# LightSaber.net
KiCad netlist of a schematic drawn in Altium Designer
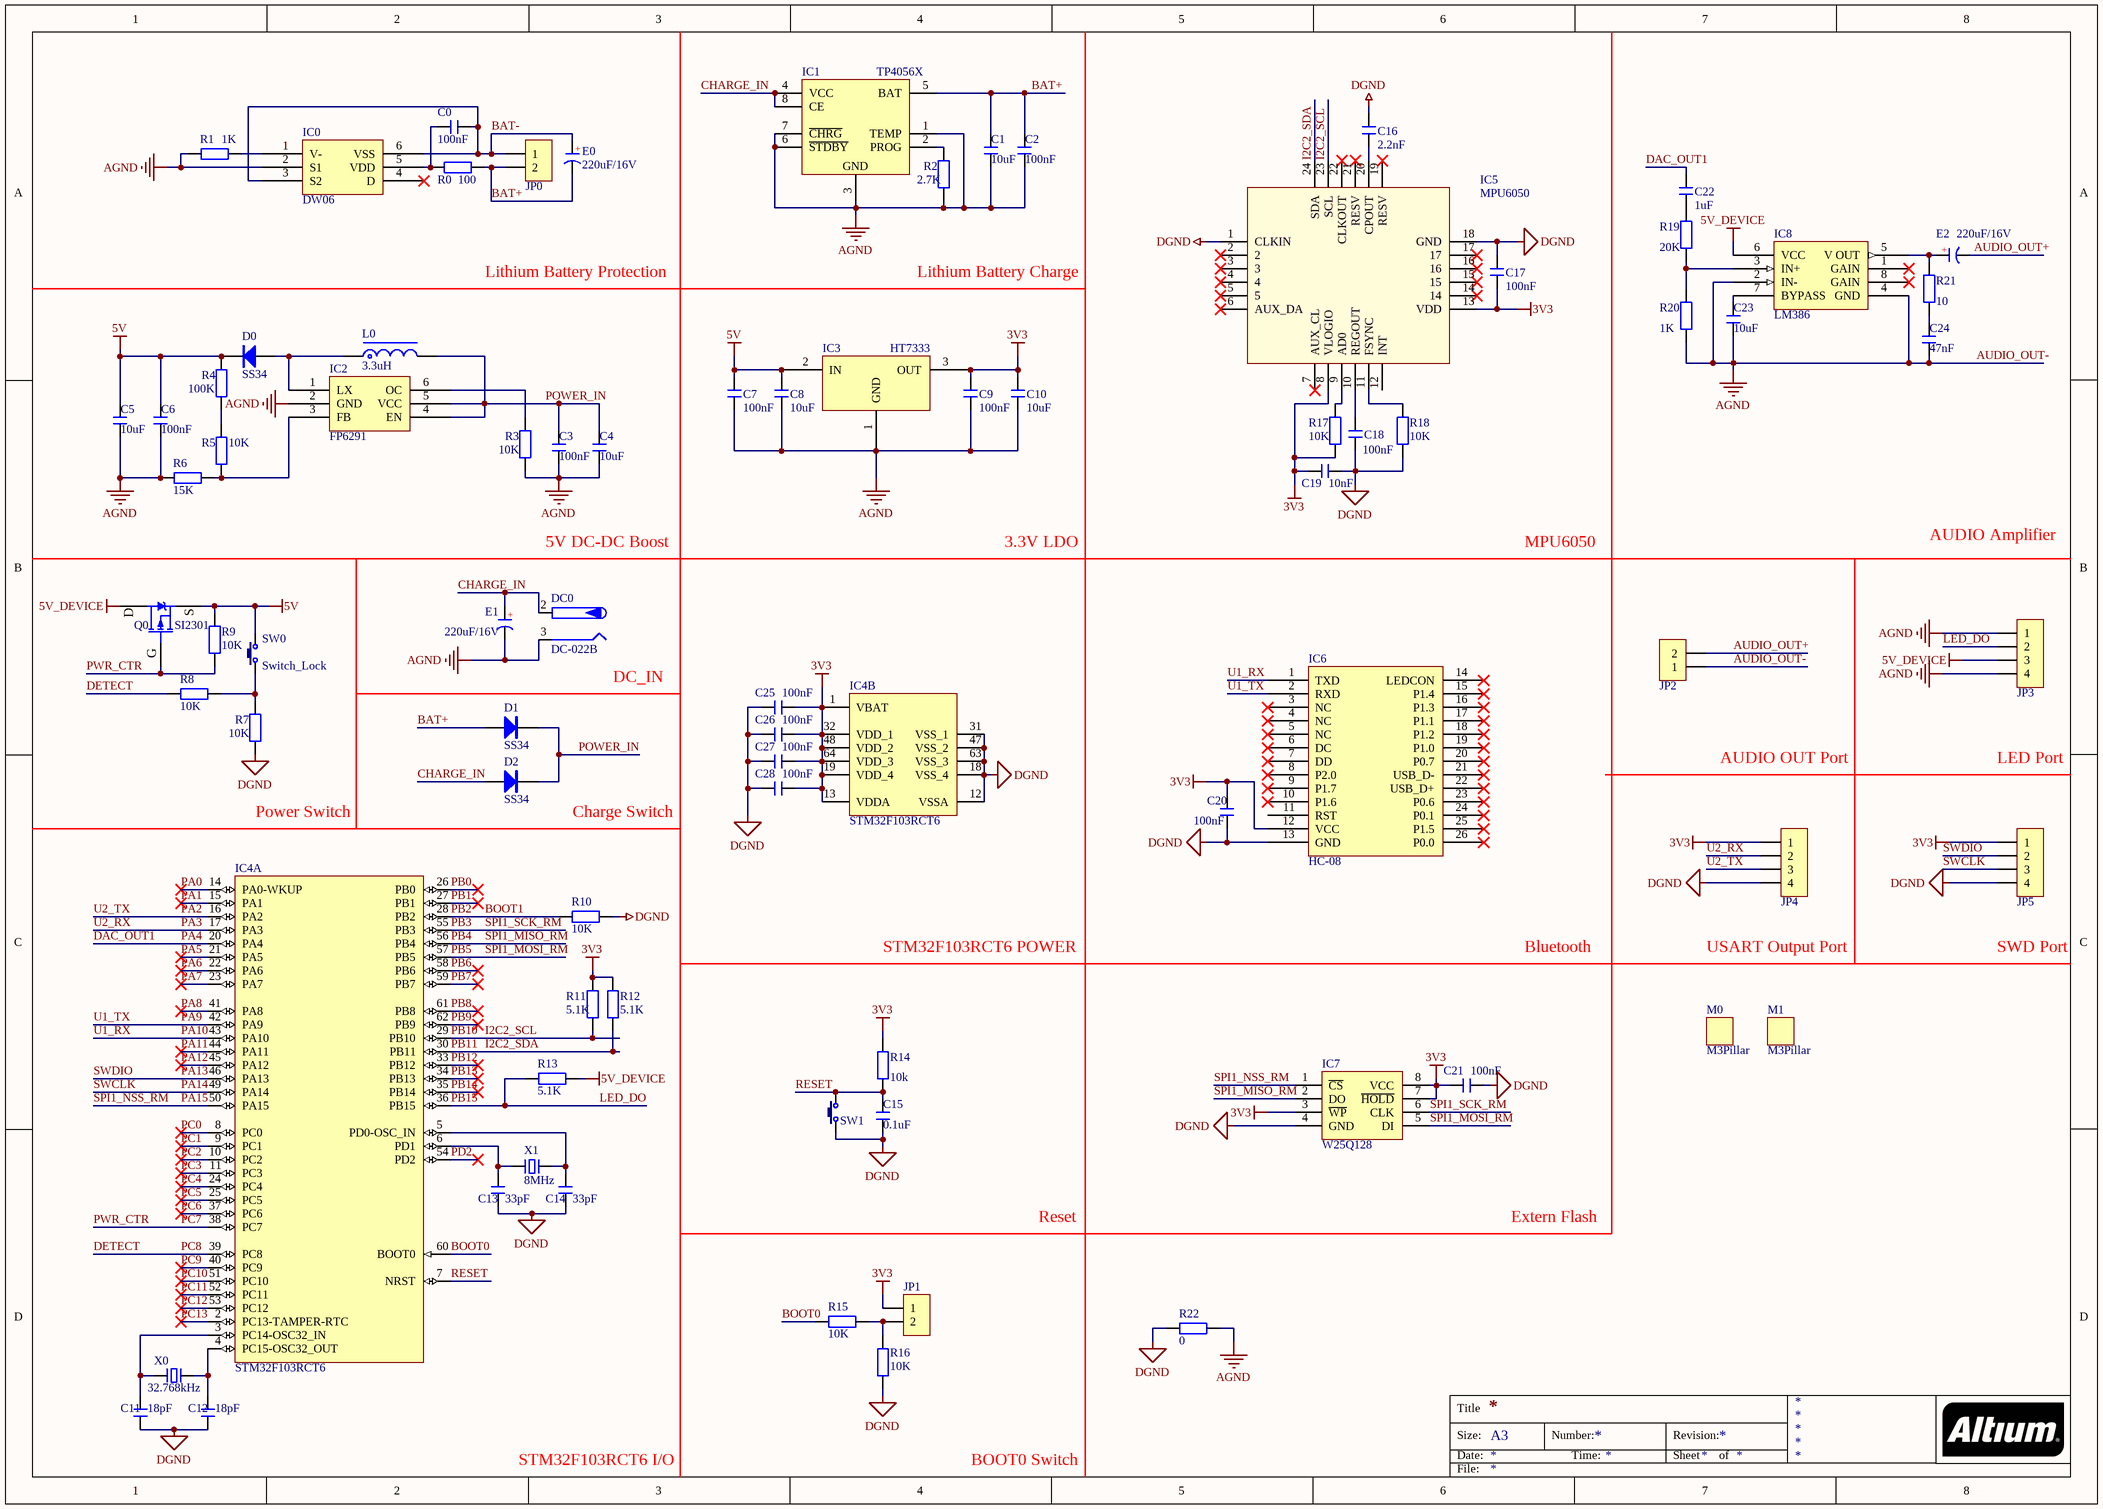
[diagram p0: LightSaber.SchDoc]

(export (version "E")
  (design (tool "Eeschema 10.0.6"))
  (components
    (comp (ref "C0")
      (value "100nF")
      (footprint "C 0603_L")
      (description "无极性贴片电容")
      (libsource (lib "0.1 - 电阻-电容-电感") (part "C"))
    )
    (comp (ref "C1")
      (value "10uF")
      (footprint "C 0603_L")
      (description "无极性贴片电容")
      (libsource (lib "0.1 - 电阻-电容-电感") (part "C"))
    )
    (comp (ref "C2")
      (value "100nF")
      (footprint "C 0603_L")
      (description "无极性贴片电容")
      (libsource (lib "0.1 - 电阻-电容-电感") (part "C"))
    )
    (comp (ref "C3")
      (value "100nF")
      (footprint "C 0603_L")
      (description "无极性贴片电容")
      (libsource (lib "0.1 - 电阻-电容-电感") (part "C"))
    )
    (comp (ref "C4")
      (value "10uF")
      (footprint "C 0603_L")
      (description "无极性贴片电容")
      (libsource (lib "0.1 - 电阻-电容-电感") (part "C"))
    )
    (comp (ref "C5")
      (value "10uF")
      (footprint "C 0603_L")
      (description "无极性贴片电容")
      (libsource (lib "0.1 - 电阻-电容-电感") (part "C"))
    )
    (comp (ref "C6")
      (value "100nF")
      (footprint "C 0603_L")
      (description "无极性贴片电容")
      (libsource (lib "0.1 - 电阻-电容-电感") (part "C"))
    )
    (comp (ref "C7")
      (value "100nF")
      (footprint "C 0603_L")
      (description "无极性贴片电容")
      (libsource (lib "0.1 - 电阻-电容-电感") (part "C"))
    )
    (comp (ref "C8")
      (value "10uF")
      (footprint "C 0603_L")
      (description "无极性贴片电容")
      (libsource (lib "0.1 - 电阻-电容-电感") (part "C"))
    )
    (comp (ref "C9")
      (value "100nF")
      (footprint "C 0603_L")
      (description "无极性贴片电容")
      (libsource (lib "0.1 - 电阻-电容-电感") (part "C"))
    )
    (comp (ref "C10")
      (value "10uF")
      (footprint "C 0603_L")
      (description "无极性贴片电容")
      (libsource (lib "0.1 - 电阻-电容-电感") (part "C"))
    )
    (comp (ref "C11")
      (value "18pF")
      (footprint "C 0603_L")
      (description "无极性贴片电容")
      (libsource (lib "0.1 - 电阻-电容-电感") (part "C"))
    )
    (comp (ref "C12")
      (value "18pF")
      (footprint "C 0603_L")
      (description "无极性贴片电容")
      (libsource (lib "0.1 - 电阻-电容-电感") (part "C"))
    )
    (comp (ref "C13")
      (value "33pF")
      (footprint "C 0603_L")
      (description "无极性贴片电容")
      (libsource (lib "0.1 - 电阻-电容-电感") (part "C"))
    )
    (comp (ref "C14")
      (value "33pF")
      (footprint "C 0603_L")
      (description "无极性贴片电容")
      (libsource (lib "0.1 - 电阻-电容-电感") (part "C"))
    )
    (comp (ref "C15")
      (value "0.1uF")
      (footprint "C 0603_L")
      (description "无极性贴片电容")
      (libsource (lib "0.1 - 电阻-电容-电感") (part "C"))
    )
    (comp (ref "C16")
      (value "2.2nF")
      (footprint "C 0603_L")
      (description "无极性贴片电容")
      (libsource (lib "0.1 - 电阻-电容-电感") (part "C"))
    )
    (comp (ref "C17")
      (value "100nF")
      (footprint "C 0603_L")
      (description "无极性贴片电容")
      (libsource (lib "0.1 - 电阻-电容-电感") (part "C"))
    )
    (comp (ref "C18")
      (value "100nF")
      (footprint "C 0603_L")
      (description "无极性贴片电容")
      (libsource (lib "0.1 - 电阻-电容-电感") (part "C"))
    )
    (comp (ref "C19")
      (value "10nF")
      (footprint "C 0603_L")
      (description "无极性贴片电容")
      (libsource (lib "0.1 - 电阻-电容-电感") (part "C"))
    )
    (comp (ref "C20")
      (value "100nF")
      (footprint "C 0603_L")
      (description "无极性贴片电容")
      (libsource (lib "0.1 - 电阻-电容-电感") (part "C"))
    )
    (comp (ref "C21")
      (value "100nF")
      (footprint "C 0603_L")
      (description "无极性贴片电容")
      (libsource (lib "0.1 - 电阻-电容-电感") (part "C"))
    )
    (comp (ref "C22")
      (value "1uF")
      (footprint "C 0603_L")
      (description "无极性贴片电容")
      (libsource (lib "0.1 - 电阻-电容-电感") (part "C"))
    )
    (comp (ref "C23")
      (value "10uF")
      (footprint "C 0603_L")
      (description "无极性贴片电容")
      (libsource (lib "0.1 - 电阻-电容-电感") (part "C"))
    )
    (comp (ref "C24")
      (value "47nF")
      (footprint "C 0603_L")
      (description "无极性贴片电容")
      (libsource (lib "0.1 - 电阻-电容-电感") (part "C"))
    )
    (comp (ref "C25")
      (value "100nF")
      (footprint "C 0603_L")
      (description "无极性贴片电容")
      (libsource (lib "0.1 - 电阻-电容-电感") (part "C"))
    )
    (comp (ref "C26")
      (value "100nF")
      (footprint "C 0603_L")
      (description "无极性贴片电容")
      (libsource (lib "0.1 - 电阻-电容-电感") (part "C"))
    )
    (comp (ref "C27")
      (value "100nF")
      (footprint "C 0603_L")
      (description "无极性贴片电容")
      (libsource (lib "0.1 - 电阻-电容-电感") (part "C"))
    )
    (comp (ref "C28")
      (value "100nF")
      (footprint "C 0603_L")
      (description "无极性贴片电容")
      (libsource (lib "0.1 - 电阻-电容-电感") (part "C"))
    )
    (comp (ref "D0")
      (value "SS34")
      (footprint "SMA")
      (description "肖特基二极管")
      (libsource (lib "0.2 -  二极管-整流桥") (part "SS34"))
    )
    (comp (ref "D1")
      (value "SS34")
      (footprint "SMA")
      (description "肖特基二极管")
      (libsource (lib "0.2 -  二极管-整流桥") (part "SS34"))
    )
    (comp (ref "D2")
      (value "SS34")
      (footprint "SMA")
      (description "肖特基二极管")
      (libsource (lib "0.2 -  二极管-整流桥") (part "SS34"))
    )
    (comp (ref "DC0") (value "DC-022B") (footprint "DC-022B") (libsource (lib "LightSaber") (part "DC-022B")))
    (comp (ref "E0")
      (value "220uF/16V")
      (footprint "CAP 2.5*6.3*7 - BK")
      (description "直插电解电容")
      (libsource (lib "0.1 - 电阻-电容-电感") (part "C-CAP"))
    )
    (comp (ref "E1")
      (value "220uF/16V")
      (footprint "CAP 2.5*6.3*7 - BK")
      (description "直插电解电容")
      (libsource (lib "0.1 - 电阻-电容-电感") (part "C-CAP"))
    )
    (comp (ref "E2")
      (value "220uF/16V")
      (footprint "CAP 2.5*6.3*7 - BK")
      (description "直插电解电容")
      (libsource (lib "") (part "C-CAP_1"))
    )
    (comp (ref "IC0") (value "DW06") (footprint "SOT23-6N") (libsource (lib "LightSaber") (part "DW06")))
    (comp (ref "IC1")
      (value "TP4056X")
      (footprint "SOP8_N")
      (description "锂电池充电管理")
      (libsource (lib "1.2 - 电源类芯片") (part "TP4056"))
    )
    (comp (ref "IC2")
      (value "FP6291")
      (footprint "SOT23-6")
      (libsource (lib "altium-import") (part "root_0_FP6291_"))
    )
    (comp (ref "IC3") (value "HT7333") (footprint "SOT89_M") (libsource (lib "LightSaber") (part "HT7333")))
    (comp (ref "IC4")
      (value "STM32F103RCT6")
      (footprint "LQFP64_N")
      (libsource (lib "2.3 - STM32 F1系列MCU 集成库") (part "STM32F103RCT6"))
    )
    (comp (ref "IC5")
      (value "MPU6050")
      (footprint "QFN_24")
      (description "三轴加速度+三轴陀螺仪")
      (libsource (lib "主集成库") (part "MPU6050"))
    )
    (comp (ref "IC6") (value "HC-08") (footprint "HC-08V20/22/41") (libsource (lib "HC-08") (part "HC-08")))
    (comp (ref "IC7")
      (value "W25Q128")
      (footprint "SOP8W_N")
      (description "外置Flash")
      (fields (field (name "版权归属") "源创客"))
      (libsource (lib "1.1 - 常见芯片") (part "W25Qxx"))
    )
    (comp (ref "IC8") (value "LM386") (footprint "SOP8") (libsource (lib "7.1 - 模拟符号") (part "LM386")))
    (comp (ref "JP0")
      (value "HDR-1X2")
      (footprint "XH2.54-LI-2P")
      (description "2P接插件")
      (fields (field (name "版权归属") "源创客"))
      (libsource (lib "") (part "Header 2_1"))
    )
    (comp (ref "JP1")
      (value "HDR-1X2")
      (footprint "HDR2.54-LI-2P")
      (description "2P接插件")
      (fields (field (name "版权归属") "源创客"))
      (libsource (lib "") (part "Header 2_1"))
    )
    (comp (ref "JP2")
      (value "HDR-1X2")
      (footprint "XH2.54-LI-2P")
      (description "2P接插件")
      (fields (field (name "版权归属") "源创客"))
      (libsource (lib "5.3 - 接插件-脚距2.54 (100mil) ") (part "Header 2"))
    )
    (comp (ref "JP3")
      (value "HDR-1X4")
      (footprint "XH2.54-LI-4P")
      (description "4P接插件")
      (fields (field (name "版权归属") "源创客"))
      (libsource (lib "5.3 - 接插件-脚距2.54 (100mil) ") (part "Header 4"))
    )
    (comp (ref "JP4")
      (value "HDR-1X4")
      (footprint "HDR2.54-LI-4P")
      (description "4P接插件")
      (fields (field (name "版权归属") "源创客"))
      (libsource (lib "5.3 - 接插件-脚距2.54 (100mil) ") (part "Header 4"))
    )
    (comp (ref "JP5")
      (value "HDR-1X4")
      (footprint "HDR2.54-LI-4P")
      (description "4P接插件")
      (fields (field (name "版权归属") "源创客"))
      (libsource (lib "5.3 - 接插件-脚距2.54 (100mil) ") (part "Header 4"))
    )
    (comp (ref "L0")
      (value "3.3uH")
      (footprint "PK0406")
      (description "工字电感")
      (libsource (lib "0.1 - 电阻-电容-电感") (part "L-PK"))
    )
    (comp (ref "M0") (value "M3Pillar") (footprint "M3x4_L") (libsource (lib "LightSaber") (part "M3Pillar")))
    (comp (ref "M1") (value "M3Pillar") (footprint "M3x4_L") (libsource (lib "LightSaber") (part "M3Pillar")))
    (comp (ref "Q0")
      (value "SI2301")
      (footprint "SOT23-3N")
      (description "P沟道场效应管")
      (libsource (lib "0.5 - 场效应管-可控硅") (part "SI2301"))
    )
    (comp (ref "R0")
      (value "100")
      (footprint "R 0603_L")
      (description "贴片电阻")
      (fields (field (name "版权归属") "黄晶宝石"))
      (libsource (lib "0.1 - 电阻-电容-电感") (part "R"))
    )
    (comp (ref "R1")
      (value "1K")
      (footprint "R 0603_L")
      (description "贴片电阻")
      (fields (field (name "版权归属") "黄晶宝石"))
      (libsource (lib "0.1 - 电阻-电容-电感") (part "R"))
    )
    (comp (ref "R2")
      (value "2.7K")
      (footprint "R 0603_L")
      (description "贴片电阻")
      (fields (field (name "版权归属") "黄晶宝石"))
      (libsource (lib "0.1 - 电阻-电容-电感") (part "R"))
    )
    (comp (ref "R3")
      (value "10K")
      (footprint "R 0603_L")
      (description "贴片电阻")
      (fields (field (name "版权归属") "黄晶宝石"))
      (libsource (lib "0.1 - 电阻-电容-电感") (part "R"))
    )
    (comp (ref "R4")
      (value "100K")
      (footprint "R 0603_L")
      (description "贴片电阻")
      (fields (field (name "版权归属") "黄晶宝石"))
      (libsource (lib "0.1 - 电阻-电容-电感") (part "R"))
    )
    (comp (ref "R5")
      (value "10K")
      (footprint "R 0603_L")
      (description "贴片电阻")
      (fields (field (name "版权归属") "黄晶宝石"))
      (libsource (lib "0.1 - 电阻-电容-电感") (part "R"))
    )
    (comp (ref "R6")
      (value "15K")
      (footprint "R 0603_L")
      (description "贴片电阻")
      (fields (field (name "版权归属") "黄晶宝石"))
      (libsource (lib "0.1 - 电阻-电容-电感") (part "R"))
    )
    (comp (ref "R7")
      (value "10K")
      (footprint "R 0603_L")
      (description "贴片电阻")
      (fields (field (name "版权归属") "黄晶宝石"))
      (libsource (lib "0.1 - 电阻-电容-电感") (part "R"))
    )
    (comp (ref "R8")
      (value "10K")
      (footprint "R 0603_L")
      (description "贴片电阻")
      (fields (field (name "版权归属") "黄晶宝石"))
      (libsource (lib "0.1 - 电阻-电容-电感") (part "R"))
    )
    (comp (ref "R9")
      (value "10K")
      (footprint "R 0603_L")
      (description "贴片电阻")
      (fields (field (name "版权归属") "黄晶宝石"))
      (libsource (lib "0.1 - 电阻-电容-电感") (part "R"))
    )
    (comp (ref "R10")
      (value "10K")
      (footprint "R 0603_L")
      (description "贴片电阻")
      (fields (field (name "版权归属") "黄晶宝石"))
      (libsource (lib "0.1 - 电阻-电容-电感") (part "R"))
    )
    (comp (ref "R11")
      (value "5.1K")
      (footprint "R 0603_L")
      (description "贴片电阻")
      (fields (field (name "版权归属") "黄晶宝石"))
      (libsource (lib "0.1 - 电阻-电容-电感") (part "R"))
    )
    (comp (ref "R12")
      (value "5.1K")
      (footprint "R 0603_L")
      (description "贴片电阻")
      (fields (field (name "版权归属") "黄晶宝石"))
      (libsource (lib "0.1 - 电阻-电容-电感") (part "R"))
    )
    (comp (ref "R13")
      (value "5.1K")
      (footprint "R 0603_L")
      (description "贴片电阻")
      (fields (field (name "版权归属") "黄晶宝石"))
      (libsource (lib "0.1 - 电阻-电容-电感") (part "R"))
    )
    (comp (ref "R14")
      (value "10k")
      (footprint "R 0603_L")
      (description "贴片电阻")
      (fields (field (name "版权归属") "黄晶宝石"))
      (libsource (lib "0.1 - 电阻-电容-电感") (part "R"))
    )
    (comp (ref "R15")
      (value "10K")
      (footprint "R 0603_L")
      (description "贴片电阻")
      (fields (field (name "版权归属") "黄晶宝石"))
      (libsource (lib "0.1 - 电阻-电容-电感") (part "R"))
    )
    (comp (ref "R16")
      (value "10K")
      (footprint "R 0603_L")
      (description "贴片电阻")
      (fields (field (name "版权归属") "黄晶宝石"))
      (libsource (lib "0.1 - 电阻-电容-电感") (part "R"))
    )
    (comp (ref "R17")
      (value "10K")
      (footprint "R 0603_L")
      (description "贴片电阻")
      (fields (field (name "版权归属") "黄晶宝石"))
      (libsource (lib "0.1 - 电阻-电容-电感") (part "R"))
    )
    (comp (ref "R18")
      (value "10K")
      (footprint "R 0603_L")
      (description "贴片电阻")
      (fields (field (name "版权归属") "黄晶宝石"))
      (libsource (lib "0.1 - 电阻-电容-电感") (part "R"))
    )
    (comp (ref "R19")
      (value "20K")
      (footprint "R 0603_L")
      (description "贴片电阻")
      (fields (field (name "版权归属") "黄晶宝石"))
      (libsource (lib "0.1 - 电阻-电容-电感") (part "R"))
    )
    (comp (ref "R20")
      (value "1K")
      (footprint "R 0603_L")
      (description "贴片电阻")
      (fields (field (name "版权归属") "黄晶宝石"))
      (libsource (lib "0.1 - 电阻-电容-电感") (part "R"))
    )
    (comp (ref "R21")
      (value "10")
      (footprint "R 0603_L")
      (description "贴片电阻")
      (fields (field (name "版权归属") "黄晶宝石"))
      (libsource (lib "0.1 - 电阻-电容-电感") (part "R"))
    )
    (comp (ref "R22")
      (value "0")
      (footprint "R 0603_L")
      (description "贴片电阻")
      (fields (field (name "版权归属") "黄晶宝石"))
      (libsource (lib "0.1 - 电阻-电容-电感") (part "R"))
    )
    (comp (ref "SW0")
      (value "Switch_Lock")
      (footprint "Switch_Lock")
      (libsource (lib "LightSaber") (part "Switch_Lock"))
    )
    (comp (ref "SW1")
      (value "3x6x5")
      (footprint "TSW SMD-3*6*2.5")
      (description "3x6轻触开关")
      (fields (field (name "版权归属") "源创客"))
      (libsource (lib "0.7 - 常用按键-开关") (part "TSW 3x6"))
    )
    (comp (ref "X0")
      (value "32.768kHz")
      (footprint "OSC 3215-2P")
      (description "2脚无源脚晶振")
      (fields (field (name "版权归属") "源创客"))
      (libsource (lib "3.4 - 保险丝-晶振") (part "XTAL-2P"))
    )
    (comp (ref "X1")
      (value "8MHz")
      (footprint "OSC 5032-2P")
      (description "2脚无源脚晶振")
      (fields (field (name "版权归属") "源创客"))
      (libsource (lib "3.4 - 保险丝-晶振") (part "XTAL-2P"))
    )
  )
  (nets
    (net (code "1") (name "/AUDIO_OUT+") (class "Default")
      (node (ref "E2") (pin "2") (pinfunction "K_2") (pintype "passive"))
      (node (ref "JP2") (pin "2") (pinfunction "2_2") (pintype "passive"))
    )
    (net (code "2") (name "/BAT+") (class "Default")
      (node (ref "C1") (pin "2") (pinfunction "2_2") (pintype "passive"))
      (node (ref "C2") (pin "2") (pinfunction "2_2") (pintype "passive"))
      (node (ref "D1") (pin "1") (pinfunction "A_1") (pintype "passive"))
      (node (ref "E0") (pin "2") (pinfunction "K_2") (pintype "passive"))
      (node (ref "IC1") (pin "5") (pinfunction "BAT_5") (pintype "passive"))
      (node (ref "JP0") (pin "2") (pinfunction "2_2") (pintype "passive"))
      (node (ref "R0") (pin "2") (pinfunction "2_2") (pintype "passive"))
    )
    (net (code "3") (name "/BAT-") (class "Default")
      (node (ref "C0") (pin "2") (pinfunction "2_2") (pintype "passive"))
      (node (ref "E0") (pin "1") (pinfunction "A_1") (pintype "passive"))
      (node (ref "IC0") (pin "3") (pinfunction "S2_3") (pintype "passive"))
      (node (ref "IC0") (pin "6") (pinfunction "VSS_6") (pintype "passive"))
      (node (ref "JP0") (pin "1") (pinfunction "1_1") (pintype "passive"))
    )
    (net (code "4") (name "/BOOT0") (class "Default")
      (node (ref "IC4") (pin "60") (pinfunction "BOOT0_60") (pintype "input"))
      (node (ref "R15") (pin "2") (pinfunction "2_2") (pintype "passive"))
    )
    (net (code "5") (name "/BOOT1") (class "Default")
      (node (ref "IC4") (pin "28") (pinfunction "PB2_28") (pintype "bidirectional"))
      (node (ref "R10") (pin "1") (pinfunction "1_1") (pintype "passive"))
    )
    (net (code "6") (name "/CHARGE_IN") (class "Default")
      (node (ref "D2") (pin "1") (pinfunction "A_1") (pintype "passive"))
      (node (ref "DC0") (pin "2") (pintype "power_in"))
      (node (ref "E1") (pin "1") (pinfunction "A_1") (pintype "passive"))
      (node (ref "IC1") (pin "4") (pinfunction "VCC_4") (pintype "passive"))
      (node (ref "IC1") (pin "8") (pinfunction "CE_8") (pintype "passive"))
    )
    (net (code "7") (name "/DAC_OUT1") (class "Default")
      (node (ref "C22") (pin "2") (pinfunction "2_2") (pintype "passive"))
      (node (ref "IC4") (pin "20") (pinfunction "PA4_20") (pintype "bidirectional"))
    )
    (net (code "8") (name "/DETECT") (class "Default")
      (node (ref "IC4") (pin "39") (pinfunction "PC8_39") (pintype "bidirectional"))
      (node (ref "R8") (pin "1") (pinfunction "1_1") (pintype "passive"))
    )
    (net (code "9") (name "/I2C2_SCL") (class "Default")
      (node (ref "IC4") (pin "29") (pinfunction "PB10_29") (pintype "bidirectional"))
      (node (ref "IC5") (pin "23") (pinfunction "SCL_23") (pintype "passive"))
      (node (ref "R11") (pin "1") (pinfunction "1_1") (pintype "passive"))
    )
    (net (code "10") (name "/I2C2_SDA") (class "Default")
      (node (ref "IC4") (pin "30") (pinfunction "PB11_30") (pintype "bidirectional"))
      (node (ref "IC5") (pin "24") (pinfunction "SDA_24") (pintype "passive"))
      (node (ref "R12") (pin "1") (pinfunction "1_1") (pintype "passive"))
    )
    (net (code "11") (name "/LED_DO") (class "Default")
      (node (ref "IC4") (pin "36") (pinfunction "PB15_36") (pintype "bidirectional"))
      (node (ref "JP3") (pin "2") (pinfunction "2_2") (pintype "passive"))
      (node (ref "R13") (pin "1") (pinfunction "1_1") (pintype "passive"))
    )
    (net (code "12") (name "/PA0") (class "Default")
      (node (ref "IC4") (pin "14") (pinfunction "PA0-WKUP_14") (pintype "bidirectional+no_connect"))
    )
    (net (code "13") (name "/PA1") (class "Default")
      (node (ref "IC4") (pin "15") (pinfunction "PA1_15") (pintype "bidirectional+no_connect"))
    )
    (net (code "14") (name "/PA2") (class "Default")
      (node (ref "IC4") (pin "16") (pinfunction "PA2_16") (pintype "bidirectional"))
      (node (ref "JP4") (pin "3") (pinfunction "3_3") (pintype "passive"))
    )
    (net (code "15") (name "/PA3") (class "Default")
      (node (ref "IC4") (pin "17") (pinfunction "PA3_17") (pintype "bidirectional"))
      (node (ref "JP4") (pin "2") (pinfunction "2_2") (pintype "passive"))
    )
    (net (code "16") (name "/PA5") (class "Default")
      (node (ref "IC4") (pin "21") (pinfunction "PA5_21") (pintype "bidirectional+no_connect"))
    )
    (net (code "17") (name "/PA6") (class "Default")
      (node (ref "IC4") (pin "22") (pinfunction "PA6_22") (pintype "bidirectional+no_connect"))
    )
    (net (code "18") (name "/PA7") (class "Default")
      (node (ref "IC4") (pin "23") (pinfunction "PA7_23") (pintype "bidirectional+no_connect"))
    )
    (net (code "19") (name "/PA8") (class "Default")
      (node (ref "IC4") (pin "41") (pinfunction "PA8_41") (pintype "bidirectional+no_connect"))
    )
    (net (code "20") (name "/PA9") (class "Default")
      (node (ref "IC4") (pin "42") (pinfunction "PA9_42") (pintype "bidirectional"))
      (node (ref "IC6") (pin "2") (pinfunction "RXD_2") (pintype "passive"))
    )
    (net (code "21") (name "/PA10") (class "Default")
      (node (ref "IC4") (pin "43") (pinfunction "PA10_43") (pintype "bidirectional"))
      (node (ref "IC6") (pin "1") (pinfunction "TXD_1") (pintype "passive"))
    )
    (net (code "22") (name "/PA11") (class "Default")
      (node (ref "IC4") (pin "44") (pinfunction "PA11_44") (pintype "bidirectional+no_connect"))
    )
    (net (code "23") (name "/PA12") (class "Default")
      (node (ref "IC4") (pin "45") (pinfunction "PA12_45") (pintype "bidirectional+no_connect"))
    )
    (net (code "24") (name "/PA13") (class "Default")
      (node (ref "IC4") (pin "46") (pinfunction "PA13_46") (pintype "bidirectional"))
      (node (ref "JP5") (pin "2") (pinfunction "2_2") (pintype "passive"))
    )
    (net (code "25") (name "/PA14") (class "Default")
      (node (ref "IC4") (pin "49") (pinfunction "PA14_49") (pintype "bidirectional"))
      (node (ref "JP5") (pin "3") (pinfunction "3_3") (pintype "passive"))
    )
    (net (code "26") (name "/PA15") (class "Default")
      (node (ref "IC4") (pin "50") (pinfunction "PA15_50") (pintype "bidirectional"))
      (node (ref "IC7") (pin "1") (pinfunction "~{CS}_1") (pintype "passive"))
    )
    (net (code "27") (name "/PB0") (class "Default")
      (node (ref "IC4") (pin "26") (pinfunction "PB0_26") (pintype "bidirectional+no_connect"))
    )
    (net (code "28") (name "/PB1") (class "Default")
      (node (ref "IC4") (pin "27") (pinfunction "PB1_27") (pintype "bidirectional+no_connect"))
    )
    (net (code "29") (name "/PB3") (class "Default")
      (node (ref "IC4") (pin "55") (pinfunction "PB3_55") (pintype "bidirectional"))
      (node (ref "IC7") (pin "6") (pinfunction "CLK_6") (pintype "passive"))
    )
    (net (code "30") (name "/PB4") (class "Default")
      (node (ref "IC4") (pin "56") (pinfunction "PB4_56") (pintype "bidirectional"))
      (node (ref "IC7") (pin "2") (pinfunction "DO_2") (pintype "passive"))
    )
    (net (code "31") (name "/PB5") (class "Default")
      (node (ref "IC4") (pin "57") (pinfunction "PB5_57") (pintype "bidirectional"))
      (node (ref "IC7") (pin "5") (pinfunction "DI_5") (pintype "passive"))
    )
    (net (code "32") (name "/PB6") (class "Default")
      (node (ref "IC4") (pin "58") (pinfunction "PB6_58") (pintype "bidirectional+no_connect"))
    )
    (net (code "33") (name "/PB7") (class "Default")
      (node (ref "IC4") (pin "59") (pinfunction "PB7_59") (pintype "bidirectional+no_connect"))
    )
    (net (code "34") (name "/PB8") (class "Default")
      (node (ref "IC4") (pin "61") (pinfunction "PB8_61") (pintype "bidirectional+no_connect"))
    )
    (net (code "35") (name "/PB9") (class "Default")
      (node (ref "IC4") (pin "62") (pinfunction "PB9_62") (pintype "bidirectional+no_connect"))
    )
    (net (code "36") (name "/PB12") (class "Default")
      (node (ref "IC4") (pin "33") (pinfunction "PB12_33") (pintype "bidirectional+no_connect"))
    )
    (net (code "37") (name "/PB13") (class "Default")
      (node (ref "IC4") (pin "34") (pinfunction "PB13_34") (pintype "bidirectional+no_connect"))
    )
    (net (code "38") (name "/PB14") (class "Default")
      (node (ref "IC4") (pin "35") (pinfunction "PB14_35") (pintype "bidirectional+no_connect"))
    )
    (net (code "39") (name "/PC0") (class "Default")
      (node (ref "IC4") (pin "8") (pinfunction "PC0_8") (pintype "bidirectional+no_connect"))
    )
    (net (code "40") (name "/PC1") (class "Default")
      (node (ref "IC4") (pin "9") (pinfunction "PC1_9") (pintype "bidirectional+no_connect"))
    )
    (net (code "41") (name "/PC2") (class "Default")
      (node (ref "IC4") (pin "10") (pinfunction "PC2_10") (pintype "bidirectional+no_connect"))
    )
    (net (code "42") (name "/PC3") (class "Default")
      (node (ref "IC4") (pin "11") (pinfunction "PC3_11") (pintype "bidirectional+no_connect"))
    )
    (net (code "43") (name "/PC4") (class "Default")
      (node (ref "IC4") (pin "24") (pinfunction "PC4_24") (pintype "bidirectional+no_connect"))
    )
    (net (code "44") (name "/PC5") (class "Default")
      (node (ref "IC4") (pin "25") (pinfunction "PC5_25") (pintype "bidirectional+no_connect"))
    )
    (net (code "45") (name "/PC6") (class "Default")
      (node (ref "IC4") (pin "37") (pinfunction "PC6_37") (pintype "bidirectional+no_connect"))
    )
    (net (code "46") (name "/PC7") (class "Default")
      (node (ref "IC4") (pin "38") (pinfunction "PC7_38") (pintype "bidirectional"))
      (node (ref "Q0") (pin "1") (pinfunction "G_1") (pintype "passive"))
      (node (ref "R9") (pin "1") (pinfunction "1_1") (pintype "passive"))
    )
    (net (code "47") (name "/PC9") (class "Default")
      (node (ref "IC4") (pin "40") (pinfunction "PC9_40") (pintype "bidirectional+no_connect"))
    )
    (net (code "48") (name "/PC10") (class "Default")
      (node (ref "IC4") (pin "51") (pinfunction "PC10_51") (pintype "bidirectional+no_connect"))
    )
    (net (code "49") (name "/PC11") (class "Default")
      (node (ref "IC4") (pin "52") (pinfunction "PC11_52") (pintype "bidirectional+no_connect"))
    )
    (net (code "50") (name "/PC12") (class "Default")
      (node (ref "IC4") (pin "53") (pinfunction "PC12_53") (pintype "bidirectional+no_connect"))
    )
    (net (code "51") (name "/PC13") (class "Default")
      (node (ref "IC4") (pin "2") (pinfunction "PC13-TAMPER-RTC_2") (pintype "bidirectional+no_connect"))
    )
    (net (code "52") (name "/PD2") (class "Default")
      (node (ref "IC4") (pin "54") (pinfunction "PD2_54") (pintype "bidirectional+no_connect"))
    )
    (net (code "53") (name "/POWER_IN") (class "Default")
      (node (ref "C3") (pin "2") (pinfunction "2_2") (pintype "passive"))
      (node (ref "C4") (pin "2") (pinfunction "2_2") (pintype "passive"))
      (node (ref "D1") (pin "2") (pinfunction "K_2") (pintype "passive"))
      (node (ref "D2") (pin "2") (pinfunction "K_2") (pintype "passive"))
      (node (ref "IC2") (pin "4") (pinfunction "EN_4") (pintype "passive"))
      (node (ref "IC2") (pin "5") (pinfunction "VCC_5") (pintype "passive"))
      (node (ref "L0") (pin "2") (pinfunction "2_2") (pintype "passive"))
    )
    (net (code "54") (name "/RESET") (class "Default")
      (node (ref "C15") (pin "2") (pinfunction "2_2") (pintype "passive"))
      (node (ref "IC4") (pin "7") (pinfunction "NRST_7") (pintype "bidirectional"))
      (node (ref "R14") (pin "1") (pinfunction "1_1") (pintype "passive"))
      (node (ref "SW1") (pin "2") (pinfunction "2_2") (pintype "passive"))
    )
    (net (code "55") (name "3V3") (class "Default")
      (node (ref "C10") (pin "2") (pinfunction "2_2") (pintype "passive"))
      (node (ref "C17") (pin "1") (pinfunction "1_1") (pintype "passive"))
      (node (ref "C19") (pin "1") (pinfunction "1_1") (pintype "passive"))
      (node (ref "C20") (pin "2") (pinfunction "2_2") (pintype "passive"))
      (node (ref "C21") (pin "1") (pinfunction "1_1") (pintype "passive"))
      (node (ref "C25") (pin "2") (pinfunction "2_2") (pintype "passive"))
      (node (ref "C26") (pin "2") (pinfunction "2_2") (pintype "passive"))
      (node (ref "C27") (pin "2") (pinfunction "2_2") (pintype "passive"))
      (node (ref "C28") (pin "2") (pinfunction "2_2") (pintype "passive"))
      (node (ref "C9") (pin "2") (pinfunction "2_2") (pintype "passive"))
      (node (ref "IC3") (pin "3") (pinfunction "OUT_3") (pintype "passive"))
      (node (ref "IC4") (pin "1") (pinfunction "VBAT_1") (pintype "power_in"))
      (node (ref "IC4") (pin "13") (pinfunction "VDDA_13") (pintype "power_in"))
      (node (ref "IC4") (pin "19") (pinfunction "VDD_4_19") (pintype "power_in"))
      (node (ref "IC4") (pin "32") (pinfunction "VDD_1_32") (pintype "power_in"))
      (node (ref "IC4") (pin "48") (pinfunction "VDD_2_48") (pintype "power_in"))
      (node (ref "IC4") (pin "64") (pinfunction "VDD_3_64") (pintype "power_in"))
      (node (ref "IC5") (pin "13") (pinfunction "VDD_13") (pintype "passive"))
      (node (ref "IC5") (pin "8") (pinfunction "VLOGIO_8") (pintype "passive"))
      (node (ref "IC6") (pin "12") (pinfunction "VCC_12") (pintype "passive"))
      (node (ref "IC7") (pin "3") (pinfunction "~{WP}_3") (pintype "passive"))
      (node (ref "IC7") (pin "7") (pinfunction "~{HOLD}_7") (pintype "passive"))
      (node (ref "IC7") (pin "8") (pinfunction "VCC_8") (pintype "passive"))
      (node (ref "JP1") (pin "1") (pinfunction "1_1") (pintype "passive"))
      (node (ref "JP4") (pin "1") (pinfunction "1_1") (pintype "passive"))
      (node (ref "JP5") (pin "1") (pinfunction "1_1") (pintype "passive"))
      (node (ref "R11") (pin "2") (pinfunction "2_2") (pintype "passive"))
      (node (ref "R12") (pin "2") (pinfunction "2_2") (pintype "passive"))
      (node (ref "R14") (pin "2") (pinfunction "2_2") (pintype "passive"))
      (node (ref "R17") (pin "1") (pinfunction "1_1") (pintype "passive"))
    )
    (net (code "56") (name "5V") (class "Default")
      (node (ref "C5") (pin "2") (pinfunction "2_2") (pintype "passive"))
      (node (ref "C6") (pin "2") (pinfunction "2_2") (pintype "passive"))
      (node (ref "C7") (pin "2") (pinfunction "2_2") (pintype "passive"))
      (node (ref "C8") (pin "2") (pinfunction "2_2") (pintype "passive"))
      (node (ref "D0") (pin "2") (pinfunction "K_2") (pintype "passive"))
      (node (ref "IC3") (pin "2") (pinfunction "IN_2") (pintype "passive"))
      (node (ref "Q0") (pin "2") (pinfunction "S_2") (pintype "passive"))
      (node (ref "R4") (pin "2") (pinfunction "2_2") (pintype "passive"))
      (node (ref "R9") (pin "2") (pinfunction "2_2") (pintype "passive"))
      (node (ref "SW0") (pin "2") (pinfunction "2_2") (pintype "passive"))
    )
    (net (code "57") (name "5V_DEVICE") (class "Default")
      (node (ref "IC8") (pin "6") (pinfunction "VCC_6") (pintype "passive"))
      (node (ref "JP3") (pin "3") (pinfunction "3_3") (pintype "passive"))
      (node (ref "Q0") (pin "3") (pinfunction "D_3") (pintype "passive"))
      (node (ref "R13") (pin "2") (pinfunction "2_2") (pintype "passive"))
    )
    (net (code "58") (name "AGND") (class "Default")
      (node (ref "C1") (pin "1") (pinfunction "1_1") (pintype "passive"))
      (node (ref "C10") (pin "1") (pinfunction "1_1") (pintype "passive"))
      (node (ref "C2") (pin "1") (pinfunction "1_1") (pintype "passive"))
      (node (ref "C23") (pin "1") (pinfunction "1_1") (pintype "passive"))
      (node (ref "C24") (pin "1") (pinfunction "1_1") (pintype "passive"))
      (node (ref "C3") (pin "1") (pinfunction "1_1") (pintype "passive"))
      (node (ref "C4") (pin "1") (pinfunction "1_1") (pintype "passive"))
      (node (ref "C5") (pin "1") (pinfunction "1_1") (pintype "passive"))
      (node (ref "C6") (pin "1") (pinfunction "1_1") (pintype "passive"))
      (node (ref "C7") (pin "1") (pinfunction "1_1") (pintype "passive"))
      (node (ref "C8") (pin "1") (pinfunction "1_1") (pintype "passive"))
      (node (ref "C9") (pin "1") (pinfunction "1_1") (pintype "passive"))
      (node (ref "DC0") (pin "3") (pintype "power_in"))
      (node (ref "E1") (pin "2") (pinfunction "K_2") (pintype "passive"))
      (node (ref "IC0") (pin "2") (pinfunction "S1_2") (pintype "passive"))
      (node (ref "IC1") (pin "1") (pinfunction "TEMP_1") (pintype "passive"))
      (node (ref "IC1") (pin "3") (pinfunction "GND_3") (pintype "passive"))
      (node (ref "IC1") (pin "6") (pinfunction "~{STDBY}_6") (pintype "passive"))
      (node (ref "IC1") (pin "7") (pinfunction "~{CHRG}_7") (pintype "passive"))
      (node (ref "IC2") (pin "2") (pinfunction "GND_2") (pintype "passive"))
      (node (ref "IC3") (pin "1") (pinfunction "GND_1") (pintype "passive"))
      (node (ref "IC8") (pin "2") (pinfunction "IN-_2") (pintype "input"))
      (node (ref "IC8") (pin "4") (pinfunction "GND_4") (pintype "power_in"))
      (node (ref "JP2") (pin "1") (pinfunction "1_1") (pintype "passive"))
      (node (ref "JP3") (pin "1") (pinfunction "1_1") (pintype "passive"))
      (node (ref "JP3") (pin "4") (pinfunction "4_4") (pintype "passive"))
      (node (ref "R1") (pin "1") (pinfunction "1_1") (pintype "passive"))
      (node (ref "R2") (pin "1") (pinfunction "1_1") (pintype "passive"))
      (node (ref "R20") (pin "1") (pinfunction "1_1") (pintype "passive"))
      (node (ref "R22") (pin "2") (pinfunction "2_2") (pintype "passive"))
      (node (ref "R3") (pin "1") (pinfunction "1_1") (pintype "passive"))
      (node (ref "R6") (pin "1") (pinfunction "1_1") (pintype "passive"))
    )
    (net (code "59") (name "DGND") (class "Default")
      (node (ref "C11") (pin "1") (pinfunction "1_1") (pintype "passive"))
      (node (ref "C12") (pin "1") (pinfunction "1_1") (pintype "passive"))
      (node (ref "C13") (pin "1") (pinfunction "1_1") (pintype "passive"))
      (node (ref "C14") (pin "1") (pinfunction "1_1") (pintype "passive"))
      (node (ref "C15") (pin "1") (pinfunction "1_1") (pintype "passive"))
      (node (ref "C16") (pin "2") (pinfunction "2_2") (pintype "passive"))
      (node (ref "C17") (pin "2") (pinfunction "2_2") (pintype "passive"))
      (node (ref "C18") (pin "1") (pinfunction "1_1") (pintype "passive"))
      (node (ref "C19") (pin "2") (pinfunction "2_2") (pintype "passive"))
      (node (ref "C20") (pin "1") (pinfunction "1_1") (pintype "passive"))
      (node (ref "C21") (pin "2") (pinfunction "2_2") (pintype "passive"))
      (node (ref "C25") (pin "1") (pinfunction "1_1") (pintype "passive"))
      (node (ref "C26") (pin "1") (pinfunction "1_1") (pintype "passive"))
      (node (ref "C27") (pin "1") (pinfunction "1_1") (pintype "passive"))
      (node (ref "C28") (pin "1") (pinfunction "1_1") (pintype "passive"))
      (node (ref "IC4") (pin "12") (pinfunction "VSSA_12") (pintype "power_in"))
      (node (ref "IC4") (pin "18") (pinfunction "VSS_4_18") (pintype "power_in"))
      (node (ref "IC4") (pin "31") (pinfunction "VSS_1_31") (pintype "power_in"))
      (node (ref "IC4") (pin "47") (pinfunction "VSS_2_47") (pintype "power_in"))
      (node (ref "IC4") (pin "63") (pinfunction "VSS_3_63") (pintype "power_in"))
      (node (ref "IC5") (pin "1") (pinfunction "CLKIN_1") (pintype "passive"))
      (node (ref "IC5") (pin "18") (pinfunction "GND_18") (pintype "passive"))
      (node (ref "IC6") (pin "13") (pinfunction "GND_13") (pintype "passive"))
      (node (ref "IC7") (pin "4") (pinfunction "GND_4") (pintype "passive"))
      (node (ref "JP4") (pin "4") (pinfunction "4_4") (pintype "passive"))
      (node (ref "JP5") (pin "4") (pinfunction "4_4") (pintype "passive"))
      (node (ref "R10") (pin "2") (pinfunction "2_2") (pintype "passive"))
      (node (ref "R16") (pin "2") (pinfunction "2_2") (pintype "passive"))
      (node (ref "R18") (pin "1") (pinfunction "1_1") (pintype "passive"))
      (node (ref "R22") (pin "1") (pinfunction "1_1") (pintype "passive"))
      (node (ref "R7") (pin "1") (pinfunction "1_1") (pintype "passive"))
      (node (ref "SW1") (pin "1") (pinfunction "1_1") (pintype "passive"))
    )
    (net (code "60") (name "Net-(C22-Pad1)") (class "Default")
      (node (ref "C22") (pin "1") (pinfunction "1_1") (pintype "passive"))
      (node (ref "R19") (pin "2") (pinfunction "2_2") (pintype "passive"))
    )
    (net (code "61") (name "Net-(C24-Pad2)") (class "Default")
      (node (ref "C24") (pin "2") (pinfunction "2_2") (pintype "passive"))
      (node (ref "R21") (pin "1") (pinfunction "1_1") (pintype "passive"))
    )
    (net (code "62") (name "Net-(D0-A)") (class "Default")
      (node (ref "D0") (pin "1") (pinfunction "A_1") (pintype "passive"))
      (node (ref "IC2") (pin "1") (pinfunction "LX_1") (pintype "passive"))
      (node (ref "L0") (pin "1") (pinfunction "1_1") (pintype "passive"))
    )
    (net (code "63") (name "Net-(E2-A)") (class "Default")
      (node (ref "E2") (pin "1") (pinfunction "A_1") (pintype "passive"))
      (node (ref "IC8") (pin "5") (pinfunction "V_OUT_5") (pintype "output"))
      (node (ref "R21") (pin "2") (pinfunction "2_2") (pintype "passive"))
    )
    (net (code "64") (name "Net-(IC0-V-)") (class "Default")
      (node (ref "IC0") (pin "1") (pinfunction "V-_1") (pintype "passive"))
      (node (ref "R1") (pin "2") (pinfunction "2_2") (pintype "passive"))
    )
    (net (code "65") (name "Net-(IC0-VDD)") (class "Default")
      (node (ref "C0") (pin "1") (pinfunction "1_1") (pintype "passive"))
      (node (ref "IC0") (pin "5") (pinfunction "VDD_5") (pintype "passive"))
      (node (ref "R0") (pin "1") (pinfunction "1_1") (pintype "passive"))
    )
    (net (code "66") (name "Net-(IC1-PROG)") (class "Default")
      (node (ref "IC1") (pin "2") (pinfunction "PROG_2") (pintype "passive"))
      (node (ref "R2") (pin "2") (pinfunction "2_2") (pintype "passive"))
    )
    (net (code "67") (name "Net-(IC2-FB)") (class "Default")
      (node (ref "IC2") (pin "3") (pinfunction "FB_3") (pintype "passive"))
      (node (ref "R5") (pin "1") (pinfunction "1_1") (pintype "passive"))
      (node (ref "R6") (pin "2") (pinfunction "2_2") (pintype "passive"))
    )
    (net (code "68") (name "Net-(IC2-OC)") (class "Default")
      (node (ref "IC2") (pin "6") (pinfunction "OC_6") (pintype "passive"))
      (node (ref "R3") (pin "2") (pinfunction "2_2") (pintype "passive"))
    )
    (net (code "69") (name "Net-(IC4A-PC14-OSC32_IN)") (class "Default")
      (node (ref "C11") (pin "2") (pinfunction "2_2") (pintype "passive"))
      (node (ref "IC4") (pin "3") (pinfunction "PC14-OSC32_IN_3") (pintype "bidirectional"))
      (node (ref "X0") (pin "1") (pinfunction "1_1") (pintype "passive"))
    )
    (net (code "70") (name "Net-(IC4A-PC15-OSC32_OUT)") (class "Default")
      (node (ref "C12") (pin "2") (pinfunction "2_2") (pintype "passive"))
      (node (ref "IC4") (pin "4") (pinfunction "PC15-OSC32_OUT_4") (pintype "bidirectional"))
      (node (ref "X0") (pin "2") (pinfunction "2_2") (pintype "passive"))
    )
    (net (code "71") (name "Net-(IC4A-PD0-OSC_IN)") (class "Default")
      (node (ref "C14") (pin "2") (pinfunction "2_2") (pintype "passive"))
      (node (ref "IC4") (pin "5") (pinfunction "PD0-OSC_IN_5") (pintype "bidirectional"))
      (node (ref "X1") (pin "2") (pinfunction "2_2") (pintype "passive"))
    )
    (net (code "72") (name "Net-(IC4A-PD1)") (class "Default")
      (node (ref "C13") (pin "2") (pinfunction "2_2") (pintype "passive"))
      (node (ref "IC4") (pin "6") (pinfunction "PD1_6") (pintype "bidirectional"))
      (node (ref "X1") (pin "1") (pinfunction "1_1") (pintype "passive"))
    )
    (net (code "73") (name "Net-(IC5-AD0)") (class "Default")
      (node (ref "IC5") (pin "9") (pinfunction "AD0_9") (pintype "passive"))
      (node (ref "R17") (pin "2") (pinfunction "2_2") (pintype "passive"))
    )
    (net (code "74") (name "Net-(IC5-CPOUT)") (class "Default")
      (node (ref "C16") (pin "1") (pinfunction "1_1") (pintype "passive"))
      (node (ref "IC5") (pin "20") (pinfunction "CPOUT_20") (pintype "passive"))
    )
    (net (code "75") (name "Net-(IC5-FSYNC)") (class "Default")
      (node (ref "IC5") (pin "11") (pinfunction "FSYNC_11") (pintype "passive"))
      (node (ref "R18") (pin "2") (pinfunction "2_2") (pintype "passive"))
    )
    (net (code "76") (name "Net-(IC5-REGOUT)") (class "Default")
      (node (ref "C18") (pin "2") (pinfunction "2_2") (pintype "passive"))
      (node (ref "IC5") (pin "10") (pinfunction "REGOUT_10") (pintype "passive"))
    )
    (net (code "77") (name "Net-(IC8-BYPASS)") (class "Default")
      (node (ref "C23") (pin "2") (pinfunction "2_2") (pintype "passive"))
      (node (ref "IC8") (pin "7") (pinfunction "BYPASS_7") (pintype "passive"))
    )
    (net (code "78") (name "Net-(IC8-IN+)") (class "Default")
      (node (ref "IC8") (pin "3") (pinfunction "IN+_3") (pintype "input"))
      (node (ref "R19") (pin "1") (pinfunction "1_1") (pintype "passive"))
      (node (ref "R20") (pin "2") (pinfunction "2_2") (pintype "passive"))
    )
    (net (code "79") (name "Net-(JP1-Pad2)") (class "Default")
      (node (ref "JP1") (pin "2") (pinfunction "2_2") (pintype "passive"))
      (node (ref "R15") (pin "1") (pinfunction "1_1") (pintype "passive"))
      (node (ref "R16") (pin "1") (pinfunction "1_1") (pintype "passive"))
    )
    (net (code "80") (name "Net-(R4-Pad1)") (class "Default")
      (node (ref "R4") (pin "1") (pinfunction "1_1") (pintype "passive"))
      (node (ref "R5") (pin "2") (pinfunction "2_2") (pintype "passive"))
    )
    (net (code "81") (name "Net-(R7-Pad2)") (class "Default")
      (node (ref "R7") (pin "2") (pinfunction "2_2") (pintype "passive"))
      (node (ref "R8") (pin "2") (pinfunction "2_2") (pintype "passive"))
      (node (ref "SW0") (pin "1") (pinfunction "1_1") (pintype "passive"))
    )
    (net (code "82") (name "unconnected-(IC0-D-Pad4)") (class "Default")
      (node (ref "IC0") (pin "4") (pinfunction "D_4") (pintype "passive+no_connect"))
    )
    (net (code "83") (name "unconnected-(IC5-AUX_CL-Pad7)") (class "Default")
      (node (ref "IC5") (pin "7") (pinfunction "AUX_CL_7") (pintype "passive+no_connect"))
    )
    (net (code "84") (name "unconnected-(IC5-AUX_DA-Pad6)") (class "Default")
      (node (ref "IC5") (pin "6") (pinfunction "AUX_DA_6") (pintype "passive+no_connect"))
    )
    (net (code "85") (name "unconnected-(IC5-CLKOUT-Pad22)") (class "Default")
      (node (ref "IC5") (pin "22") (pinfunction "CLKOUT_22") (pintype "passive+no_connect"))
    )
    (net (code "86") (name "unconnected-(IC5-INT-Pad12)") (class "Default")
      (node (ref "IC5") (pin "12") (pinfunction "INT_12") (pintype "passive"))
    )
    (net (code "87") (name "unconnected-(IC5-Pad2)") (class "Default")
      (node (ref "IC5") (pin "2") (pinfunction "2_2") (pintype "passive+no_connect"))
    )
    (net (code "88") (name "unconnected-(IC5-Pad3)") (class "Default")
      (node (ref "IC5") (pin "3") (pinfunction "3_3") (pintype "passive+no_connect"))
    )
    (net (code "89") (name "unconnected-(IC5-Pad4)") (class "Default")
      (node (ref "IC5") (pin "4") (pinfunction "4_4") (pintype "passive+no_connect"))
    )
    (net (code "90") (name "unconnected-(IC5-Pad5)") (class "Default")
      (node (ref "IC5") (pin "5") (pinfunction "5_5") (pintype "passive+no_connect"))
    )
    (net (code "91") (name "unconnected-(IC5-Pad14)") (class "Default")
      (node (ref "IC5") (pin "14") (pinfunction "14_14") (pintype "passive+no_connect"))
    )
    (net (code "92") (name "unconnected-(IC5-Pad15)") (class "Default")
      (node (ref "IC5") (pin "15") (pinfunction "15_15") (pintype "passive+no_connect"))
    )
    (net (code "93") (name "unconnected-(IC5-Pad16)") (class "Default")
      (node (ref "IC5") (pin "16") (pinfunction "16_16") (pintype "passive+no_connect"))
    )
    (net (code "94") (name "unconnected-(IC5-Pad17)") (class "Default")
      (node (ref "IC5") (pin "17") (pinfunction "17_17") (pintype "passive+no_connect"))
    )
    (net (code "95") (name "unconnected-(IC5-RESV-Pad19)") (class "Default")
      (node (ref "IC5") (pin "19") (pinfunction "RESV_19") (pintype "passive+no_connect"))
    )
    (net (code "96") (name "unconnected-(IC5-RESV-Pad21)") (class "Default")
      (node (ref "IC5") (pin "21") (pinfunction "RESV_21") (pintype "passive+no_connect"))
    )
    (net (code "97") (name "unconnected-(IC6-DC-Pad6)") (class "Default")
      (node (ref "IC6") (pin "6") (pinfunction "DC_6") (pintype "passive+no_connect"))
    )
    (net (code "98") (name "unconnected-(IC6-DD-Pad7)") (class "Default")
      (node (ref "IC6") (pin "7") (pinfunction "DD_7") (pintype "passive+no_connect"))
    )
    (net (code "99") (name "unconnected-(IC6-LEDCON-Pad14)") (class "Default")
      (node (ref "IC6") (pin "14") (pinfunction "LEDCON_14") (pintype "passive+no_connect"))
    )
    (net (code "100") (name "unconnected-(IC6-NC-Pad3)") (class "Default")
      (node (ref "IC6") (pin "3") (pinfunction "NC_3") (pintype "passive+no_connect"))
    )
    (net (code "101") (name "unconnected-(IC6-NC-Pad4)") (class "Default")
      (node (ref "IC6") (pin "4") (pinfunction "NC_4") (pintype "passive+no_connect"))
    )
    (net (code "102") (name "unconnected-(IC6-NC-Pad5)") (class "Default")
      (node (ref "IC6") (pin "5") (pinfunction "NC_5") (pintype "passive+no_connect"))
    )
    (net (code "103") (name "unconnected-(IC6-P0.0-Pad26)") (class "Default")
      (node (ref "IC6") (pin "26") (pinfunction "P0.0_26") (pintype "passive+no_connect"))
    )
    (net (code "104") (name "unconnected-(IC6-P0.1-Pad24)") (class "Default")
      (node (ref "IC6") (pin "24") (pinfunction "P0.1_24") (pintype "passive+no_connect"))
    )
    (net (code "105") (name "unconnected-(IC6-P0.6-Pad23)") (class "Default")
      (node (ref "IC6") (pin "23") (pinfunction "P0.6_23") (pintype "passive+no_connect"))
    )
    (net (code "106") (name "unconnected-(IC6-P0.7-Pad20)") (class "Default")
      (node (ref "IC6") (pin "20") (pinfunction "P0.7_20") (pintype "passive+no_connect"))
    )
    (net (code "107") (name "unconnected-(IC6-P1.0-Pad19)") (class "Default")
      (node (ref "IC6") (pin "19") (pinfunction "P1.0_19") (pintype "passive+no_connect"))
    )
    (net (code "108") (name "unconnected-(IC6-P1.1-Pad17)") (class "Default")
      (node (ref "IC6") (pin "17") (pinfunction "P1.1_17") (pintype "passive+no_connect"))
    )
    (net (code "109") (name "unconnected-(IC6-P1.2-Pad18)") (class "Default")
      (node (ref "IC6") (pin "18") (pinfunction "P1.2_18") (pintype "passive+no_connect"))
    )
    (net (code "110") (name "unconnected-(IC6-P1.3-Pad16)") (class "Default")
      (node (ref "IC6") (pin "16") (pinfunction "P1.3_16") (pintype "passive+no_connect"))
    )
    (net (code "111") (name "unconnected-(IC6-P1.4-Pad15)") (class "Default")
      (node (ref "IC6") (pin "15") (pinfunction "P1.4_15") (pintype "passive+no_connect"))
    )
    (net (code "112") (name "unconnected-(IC6-P1.5-Pad25)") (class "Default")
      (node (ref "IC6") (pin "25") (pinfunction "P1.5_25") (pintype "passive+no_connect"))
    )
    (net (code "113") (name "unconnected-(IC6-P1.6-Pad10)") (class "Default")
      (node (ref "IC6") (pin "10") (pinfunction "P1.6_10") (pintype "passive+no_connect"))
    )
    (net (code "114") (name "unconnected-(IC6-P1.7-Pad9)") (class "Default")
      (node (ref "IC6") (pin "9") (pinfunction "P1.7_9") (pintype "passive+no_connect"))
    )
    (net (code "115") (name "unconnected-(IC6-P2.0-Pad8)") (class "Default")
      (node (ref "IC6") (pin "8") (pinfunction "P2.0_8") (pintype "passive+no_connect"))
    )
    (net (code "116") (name "unconnected-(IC6-RST-Pad11)") (class "Default")
      (node (ref "IC6") (pin "11") (pinfunction "RST_11") (pintype "passive"))
    )
    (net (code "117") (name "unconnected-(IC6-USB_D+-Pad22)") (class "Default")
      (node (ref "IC6") (pin "22") (pinfunction "USB_D+_22") (pintype "passive+no_connect"))
    )
    (net (code "118") (name "unconnected-(IC6-USB_D--Pad21)") (class "Default")
      (node (ref "IC6") (pin "21") (pinfunction "USB_D-_21") (pintype "passive+no_connect"))
    )
    (net (code "119") (name "unconnected-(IC8-GAIN-Pad1)") (class "Default")
      (node (ref "IC8") (pin "1") (pinfunction "GAIN_1") (pintype "passive+no_connect"))
    )
    (net (code "120") (name "unconnected-(IC8-GAIN-Pad8)") (class "Default")
      (node (ref "IC8") (pin "8") (pinfunction "GAIN_8") (pintype "passive+no_connect"))
    )
  )
)
